# sheet3_nRF52832.net
KiCad netlist of a schematic drawn in Altium Designer
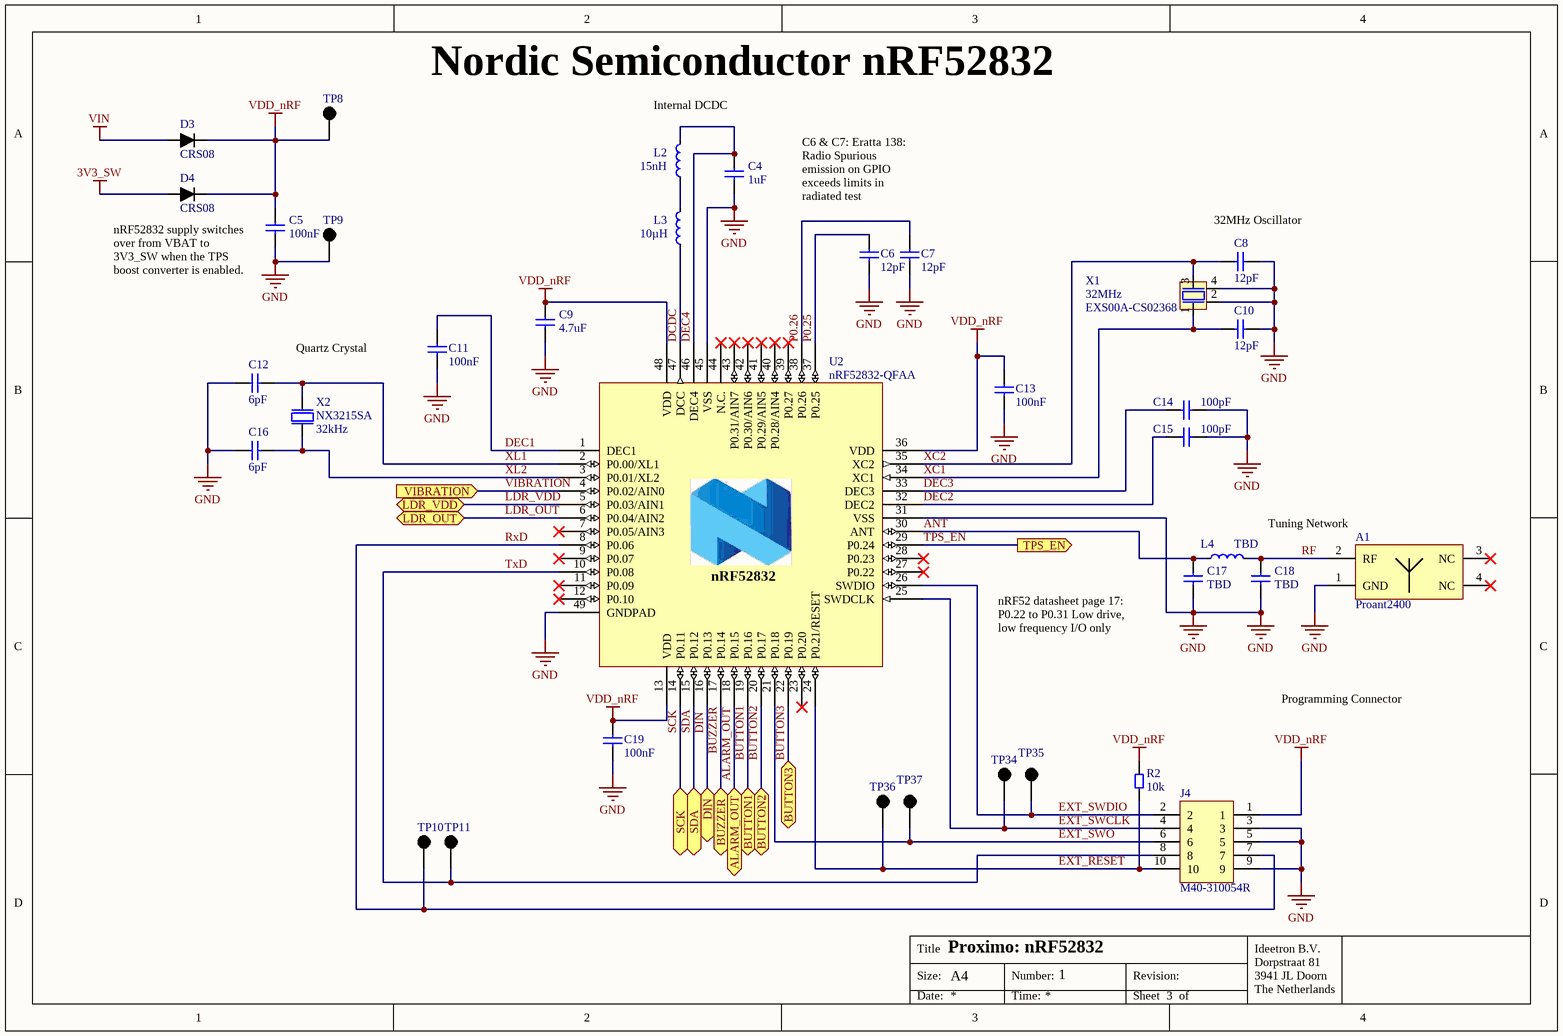
[diagram p0: sheet3_nRF52832.SchDoc]

(export (version "E")
  (design (tool "Eeschema 10.0.6"))
  (components
    (comp (ref "A1")
      (value "Proant2400")
      (footprint "Proant2400")
      (description "Onboard SMD 2400 MHz Antenna for BLE, WLAN/Wifi")
      (fields (field (name "MANUFACTURER") "Proant") (field (name "MANUFACTURER PART NUMBER") "PRO-OB-440"))
      (libsource (lib "Schlib") (part "Proant2400"))
    )
    (comp (ref "C4")
      (value "1uF")
      (footprint "CAP0603_GR18_MURATA")
      (description "Capacitor 1uF X5R 0603 Murata")
      (fields
        (field (name "MANUFACTURER") "Murata")
        (field (name "MANUFACTURER PART NUMBER") "GRM188R61E105KA12D")
      )
      (libsource (lib "Schlib") (part "CAP_0603_1uF"))
    )
    (comp (ref "C5")
      (value "100nF")
      (footprint "CAP0603_GCx18_MURATA")
      (description "Capacitor 0603 100nF")
      (fields
        (field (name "MANUFACTURER") "Murata")
        (field (name "MANUFACTURER PART NUMBER") "GCJ188R71C104KA01D")
      )
      (libsource (lib "Schlib") (part "CAP_0603_100nF"))
    )
    (comp (ref "C6")
      (value "12pF")
      (footprint "CAP0402_GCx15_Murata")
      (description "Capacitor NP0 0402")
      (fields
        (field (name "MANUFACTURER") "Murata")
        (field (name "MANUFACTURER PART NUMBER") "GCM1555C1H120JA16D")
      )
      (libsource (lib "Schlib") (part "CAP_0402_12pF"))
    )
    (comp (ref "C7")
      (value "12pF")
      (footprint "CAP0402_GCx15_Murata")
      (description "Capacitor NP0 0402")
      (fields
        (field (name "MANUFACTURER") "Murata")
        (field (name "MANUFACTURER PART NUMBER") "GCM1555C1H120JA16D")
      )
      (libsource (lib "Schlib") (part "CAP_0402_12pF"))
    )
    (comp (ref "C8")
      (value "12pF")
      (footprint "CAP0402_GCx15_Murata")
      (description "Capacitor NP0 0402")
      (fields
        (field (name "MANUFACTURER") "Murata")
        (field (name "MANUFACTURER PART NUMBER") "GCM1555C1H120JA16D")
      )
      (libsource (lib "Schlib") (part "CAP_0402_12pF"))
    )
    (comp (ref "C9")
      (value "4.7uF")
      (footprint "CAP0603_GR18_MURATA")
      (description "Capacitor X5R 0603 Murata")
      (fields
        (field (name "MANUFACTURER") "Murata")
        (field (name "MANUFACTURER PART NUMBER") "GRM188R60J475KE19D")
      )
      (libsource (lib "Schlib") (part "CAP_0603_4u7"))
    )
    (comp (ref "C10")
      (value "12pF")
      (footprint "CAP0402_GCx15_Murata")
      (description "Capacitor NP0 0402")
      (fields
        (field (name "MANUFACTURER") "Murata")
        (field (name "MANUFACTURER PART NUMBER") "GCM1555C1H120JA16D")
      )
      (libsource (lib "Schlib") (part "CAP_0402_12pF"))
    )
    (comp (ref "C11")
      (value "100nF")
      (footprint "CAP0603_GCx18_MURATA")
      (description "Capacitor 0603 100nF")
      (fields
        (field (name "MANUFACTURER") "Murata")
        (field (name "MANUFACTURER PART NUMBER") "GCJ188R71C104KA01D")
      )
      (libsource (lib "Schlib") (part "CAP_0603_100nF"))
    )
    (comp (ref "C12")
      (value "6pF")
      (footprint "CAP0603_GCx18_MURATA")
      (description "Capacitor NP0 0603 50V")
      (fields (field (name "PART NUMBER") "GCM1885C1H6R0CA16D") (field (name "MANUFACTURER") "Murata"))
      (libsource (lib "Schlib") (part "CAP_0603_6pF"))
    )
    (comp (ref "C13")
      (value "100nF")
      (footprint "CAP0603_GCx18_MURATA")
      (description "Capacitor 0603 100nF")
      (fields
        (field (name "MANUFACTURER") "Murata")
        (field (name "MANUFACTURER PART NUMBER") "GCJ188R71C104KA01D")
      )
      (libsource (lib "Schlib") (part "CAP_0603_100nF"))
    )
    (comp (ref "C14")
      (value "100pF")
      (footprint "CAP0603_GCx18_MURATA")
      (description "Capacitor 100pF 0603 NP0")
      (fields
        (field (name "MANUFACTURER") "Murata")
        (field (name "MANUFACTURER PART NUMBER") "GCM1885C1H101JA16D")
      )
      (libsource (lib "Schlib") (part "CAP_0603_100pF"))
    )
    (comp (ref "C15")
      (value "100pF")
      (footprint "CAP0603_GCx18_MURATA")
      (description "Capacitor 100pF 0603 NP0")
      (fields
        (field (name "MANUFACTURER") "Murata")
        (field (name "MANUFACTURER PART NUMBER") "GCM1885C1H101JA16D")
      )
      (libsource (lib "Schlib") (part "CAP_0603_100pF"))
    )
    (comp (ref "C16")
      (value "6pF")
      (footprint "CAP0603_GCx18_MURATA")
      (description "Capacitor NP0 0603 50V")
      (fields (field (name "PART NUMBER") "GCM1885C1H6R0CA16D") (field (name "MANUFACTURER") "Murata"))
      (libsource (lib "Schlib") (part "CAP_0603_6pF"))
    )
    (comp (ref "C17")
      (value "TBD")
      (footprint "CAPC1005X04L")
      (description "Capacitor, 0402")
      (libsource (lib "Schlib") (part "CAP_0402"))
    )
    (comp (ref "C18")
      (value "TBD")
      (footprint "CAPC1005X04L")
      (description "Capacitor, 0402")
      (libsource (lib "Schlib") (part "CAP_0402"))
    )
    (comp (ref "C19")
      (value "100nF")
      (footprint "CAP0603_GCx18_MURATA")
      (description "Capacitor 0603 100nF")
      (fields
        (field (name "MANUFACTURER") "Murata")
        (field (name "MANUFACTURER PART NUMBER") "GCJ188R71C104KA01D")
      )
      (libsource (lib "Schlib") (part "CAP_0603_100nF"))
    )
    (comp (ref "D3")
      (value "CRS08")
      (footprint "SOD-123F")
      (description "CRS08 Schottky Diode")
      (fields (field (name "MANUFACTURER") "Tohsiba"))
      (libsource (lib "Schlib") (part "CRS08 Schottky Diode"))
    )
    (comp (ref "D4")
      (value "CRS08")
      (footprint "SOD-123F")
      (description "CRS08 Schottky Diode")
      (fields (field (name "MANUFACTURER") "Tohsiba"))
      (libsource (lib "Schlib") (part "CRS08 Schottky Diode"))
    )
    (comp (ref "J4")
      (value "M40-310054R")
      (footprint "Harwin connector")
      (description "Harwin connector 2Rows x 6 contacts M40-3100545R")
      (fields (field (name "MANUFACTURER") "Harwin"))
      (libsource (lib "Schlib") (part "Harwin Connector"))
    )
    (comp (ref "L2")
      (value "15nH")
      (footprint "WE-MK_0402A")
      (description "WE-MK Multilayer Ceramic SMD Inductor, size 0402A, 15nH")
      (fields
        (field (name "PARTNUMBER") "744784115A")
        (field (name "MANUFACTURER") "Wurth Elektronik")
        (field (name "PUBLISHER") "Wurth Elektronik")
      )
      (libsource (lib "Schlib") (part "WE-MK, 744784115A"))
    )
    (comp (ref "L3")
      (value "10µH")
      (footprint "74479777xxx_0805")
      (description "WE-PMI Power Multilayer Inductor, L= 10.0µH")
      (fields
        (field (name "PARTNO") "74479777310A")
        (field (name "MANUFACTURER") "Wurth Elektronik")
        (field (name "CREATED BY") "Baojun Chen")
      )
      (libsource (lib "Schlib") (part "WE-PMI 0805, 74479777310A"))
    )
    (comp (ref "L4")
      (value "TBD")
      (footprint "INDC1005X04L")
      (description "High frequency chip inductor")
      (fields (field (name "2ND SOURCE PART NUMBER") "658-1328"))
      (libsource (lib "Schlib") (part "IND_0402"))
    )
    (comp (ref "R2")
      (value "10k")
      (footprint "RES0603VISHAY")
      (description "SMD Resistor 10k 0603")
      (fields
        (field (name "MANUFACTURER") "Vishay")
        (field (name "MANUFACTURER PART NUMBER") "CRCW060310K0FKTABC")
      )
      (libsource (lib "Schlib") (part "Resistor_10k"))
    )
    (comp (ref "TP8")
      (value "testpad")
      (footprint "TestPad")
      (description "Signal probe pad")
      (libsource (lib "Schlib") (part "TestPad"))
    )
    (comp (ref "TP9")
      (value "testpad")
      (footprint "TestPad")
      (description "Signal probe pad")
      (libsource (lib "Schlib") (part "TestPad"))
    )
    (comp (ref "TP10")
      (value "testpad")
      (footprint "TestPad")
      (description "Signal probe pad")
      (libsource (lib "Schlib") (part "TestPad"))
    )
    (comp (ref "TP11")
      (value "testpad")
      (footprint "TestPad")
      (description "Signal probe pad")
      (libsource (lib "Schlib") (part "TestPad"))
    )
    (comp (ref "TP34")
      (value "testpad")
      (footprint "TestPad")
      (description "Signal probe pad")
      (libsource (lib "Schlib") (part "TestPad"))
    )
    (comp (ref "TP35")
      (value "testpad")
      (footprint "TestPad")
      (description "Signal probe pad")
      (libsource (lib "Schlib") (part "TestPad"))
    )
    (comp (ref "TP36")
      (value "testpad")
      (footprint "TestPad")
      (description "Signal probe pad")
      (libsource (lib "Schlib") (part "TestPad"))
    )
    (comp (ref "TP37")
      (value "testpad")
      (footprint "TestPad")
      (description "Signal probe pad")
      (libsource (lib "Schlib") (part "TestPad"))
    )
    (comp (ref "U2")
      (value "nRF52832-QFAA")
      (footprint "QFN40P600X600X90-48N")
      (description "Multi-protocol Bluetooth Low Energy, ANT and 2.4GHz proprietary system-on-chip")
      (fields
        (field (name "MANUFACTURER") "Nordic Semiconductor")
        (field (name "PUBLISHER") "Nordic Semiconductor")
      )
      (libsource (lib "Schlib") (part "nRF52832_QFAA"))
    )
    (comp (ref "X1")
      (value "EXS00A-CS02368")
      (footprint "NDK-32MHz-XTAL")
      (description "NDK  NX3225SA 32MHz Oscillator")
      (fields
        (field (name "MANUFACTURER") "NDK")
        (field (name "MANUFACTURER PART NUMBER") "NX3225SA")
        (field (name "FREQUENCY") "32MHz")
      )
      (libsource (lib "Schlib") (part "NDK_32MHZ_OCILLATOR"))
    )
    (comp (ref "X2")
      (value "NX3215SA")
      (footprint "XTAL_3215")
      (description "XTAL SMD 3215, 32.768kHz, Cl=9pF, Total Tol: ±50ppm")
      (fields
        (field (name "PART NUMBER") "XTAL_FC-135 32.768k")
        (field (name "MANUFACTURER") "NDK")
        (field (name "FREQUENCY") "32kHz")
      )
      (libsource (lib "Schlib") (part "NDK_32kHz"))
    )
  )
  (nets
    (net (code "1") (name "/ALARM_OUT") (class "Default")
      (node (ref "U2") (pin "18") (pinfunction "P0.15_18") (pintype "bidirectional"))
    )
    (net (code "2") (name "/ANT") (class "Default")
      (node (ref "C17") (pin "2") (pinfunction "2_2") (pintype "passive"))
      (node (ref "L4") (pin "1") (pinfunction "1_1") (pintype "passive"))
      (node (ref "U2") (pin "30") (pinfunction "ANT_30") (pintype "bidirectional"))
    )
    (net (code "3") (name "/BUTTON1") (class "Default")
      (node (ref "U2") (pin "19") (pinfunction "P0.16_19") (pintype "bidirectional"))
    )
    (net (code "4") (name "/BUTTON2") (class "Default")
      (node (ref "U2") (pin "20") (pinfunction "P0.17_20") (pintype "bidirectional"))
    )
    (net (code "5") (name "/BUTTON3") (class "Default")
      (node (ref "U2") (pin "22") (pinfunction "P0.19_22") (pintype "bidirectional"))
    )
    (net (code "6") (name "/BUZZER") (class "Default")
      (node (ref "U2") (pin "17") (pinfunction "P0.14_17") (pintype "bidirectional"))
    )
    (net (code "7") (name "/DCDC") (class "Default")
      (node (ref "L3") (pin "1") (pinfunction "1_1") (pintype "passive"))
      (node (ref "U2") (pin "47") (pinfunction "DCC_47") (pintype "output"))
    )
    (net (code "8") (name "/DEC1") (class "Default")
      (node (ref "C11") (pin "2") (pinfunction "2_2") (pintype "passive"))
      (node (ref "U2") (pin "1") (pinfunction "DEC1_1") (pintype "power_in"))
    )
    (net (code "9") (name "/DEC2") (class "Default")
      (node (ref "C15") (pin "1") (pinfunction "1_1") (pintype "passive"))
      (node (ref "U2") (pin "32") (pinfunction "DEC2_32") (pintype "power_in"))
    )
    (net (code "10") (name "/DEC3") (class "Default")
      (node (ref "C14") (pin "1") (pinfunction "1_1") (pintype "passive"))
      (node (ref "U2") (pin "33") (pinfunction "DEC3_33") (pintype "power_in"))
    )
    (net (code "11") (name "/DEC4") (class "Default")
      (node (ref "C4") (pin "2") (pinfunction "2_2") (pintype "passive"))
      (node (ref "L2") (pin "2") (pinfunction "2_2") (pintype "passive"))
      (node (ref "U2") (pin "46") (pinfunction "DEC4_46") (pintype "power_in"))
    )
    (net (code "12") (name "/DIN") (class "Default")
      (node (ref "U2") (pin "16") (pinfunction "P0.13_16") (pintype "bidirectional"))
    )
    (net (code "13") (name "/EXT_RESET") (class "Default")
      (node (ref "J4") (pin "10") (pinfunction "10_10") (pintype "passive"))
      (node (ref "R2") (pin "1") (pinfunction "1_1") (pintype "passive"))
      (node (ref "TP36") (pin "1") (pinfunction "1_1") (pintype "passive"))
      (node (ref "U2") (pin "24") (pinfunction "P0.21/RESET_24") (pintype "bidirectional"))
    )
    (net (code "14") (name "/EXT_SWCLK") (class "Default")
      (node (ref "J4") (pin "4") (pinfunction "4_4") (pintype "passive"))
      (node (ref "TP34") (pin "1") (pinfunction "1_1") (pintype "passive"))
      (node (ref "U2") (pin "25") (pinfunction "SWDCLK_25") (pintype "input"))
    )
    (net (code "15") (name "/EXT_SWDIO") (class "Default")
      (node (ref "J4") (pin "2") (pinfunction "2_2") (pintype "passive"))
      (node (ref "TP35") (pin "1") (pinfunction "1_1") (pintype "passive"))
      (node (ref "U2") (pin "26") (pinfunction "SWDIO_26") (pintype "bidirectional"))
    )
    (net (code "16") (name "/EXT_SWO") (class "Default")
      (node (ref "J4") (pin "6") (pinfunction "6_6") (pintype "passive"))
      (node (ref "TP37") (pin "1") (pinfunction "1_1") (pintype "passive"))
      (node (ref "U2") (pin "21") (pinfunction "P0.18_21") (pintype "bidirectional"))
    )
    (net (code "17") (name "/LDR_OUT") (class "Default")
      (node (ref "U2") (pin "6") (pinfunction "P0.04/AIN2_6") (pintype "bidirectional"))
    )
    (net (code "18") (name "/LDR_VDD") (class "Default")
      (node (ref "U2") (pin "5") (pinfunction "P0.03/AIN1_5") (pintype "bidirectional"))
    )
    (net (code "19") (name "/P0.25") (class "Default")
      (node (ref "C6") (pin "2") (pinfunction "2_2") (pintype "passive"))
      (node (ref "U2") (pin "37") (pinfunction "P0.25_37") (pintype "bidirectional"))
    )
    (net (code "20") (name "/P0.26") (class "Default")
      (node (ref "C7") (pin "2") (pinfunction "2_2") (pintype "passive"))
      (node (ref "U2") (pin "38") (pinfunction "P0.26_38") (pintype "bidirectional"))
    )
    (net (code "21") (name "/RF") (class "Default")
      (node (ref "A1") (pin "2") (pinfunction "RF_2") (pintype "passive"))
      (node (ref "C18") (pin "2") (pinfunction "2_2") (pintype "passive"))
      (node (ref "L4") (pin "2") (pinfunction "2_2") (pintype "passive"))
    )
    (net (code "22") (name "/RxD") (class "Default")
      (node (ref "J4") (pin "7") (pinfunction "7_7") (pintype "passive"))
      (node (ref "TP10") (pin "1") (pinfunction "1_1") (pintype "passive"))
      (node (ref "U2") (pin "8") (pinfunction "P0.06_8") (pintype "bidirectional"))
    )
    (net (code "23") (name "/SCK") (class "Default")
      (node (ref "U2") (pin "14") (pinfunction "P0.11_14") (pintype "bidirectional"))
    )
    (net (code "24") (name "/SDA") (class "Default")
      (node (ref "U2") (pin "15") (pinfunction "P0.12_15") (pintype "bidirectional"))
    )
    (net (code "25") (name "/TPS_EN") (class "Default")
      (node (ref "U2") (pin "29") (pinfunction "P0.24_29") (pintype "bidirectional"))
    )
    (net (code "26") (name "/TxD") (class "Default")
      (node (ref "J4") (pin "8") (pinfunction "8_8") (pintype "passive"))
      (node (ref "TP11") (pin "1") (pinfunction "1_1") (pintype "passive"))
      (node (ref "U2") (pin "10") (pinfunction "P0.08_10") (pintype "bidirectional"))
    )
    (net (code "27") (name "/VIBRATION") (class "Default")
      (node (ref "U2") (pin "4") (pinfunction "P0.02/AIN0_4") (pintype "bidirectional"))
    )
    (net (code "28") (name "/XC1") (class "Default")
      (node (ref "C10") (pin "2") (pinfunction "2_2") (pintype "passive"))
      (node (ref "U2") (pin "34") (pinfunction "XC1_34") (pintype "input"))
      (node (ref "X1") (pin "1") (pinfunction "inp_1") (pintype "passive"))
    )
    (net (code "29") (name "/XC2") (class "Default")
      (node (ref "C8") (pin "2") (pinfunction "2_2") (pintype "passive"))
      (node (ref "U2") (pin "35") (pinfunction "XC2_35") (pintype "output"))
      (node (ref "X1") (pin "3") (pinfunction "out_3") (pintype "passive"))
    )
    (net (code "30") (name "/XL1") (class "Default")
      (node (ref "C12") (pin "2") (pinfunction "2_2") (pintype "passive"))
      (node (ref "U2") (pin "2") (pinfunction "P0.00/XL1_2") (pintype "bidirectional"))
      (node (ref "X2") (pin "2") (pinfunction "out_2") (pintype "passive"))
    )
    (net (code "31") (name "/XL2") (class "Default")
      (node (ref "C16") (pin "2") (pinfunction "2_2") (pintype "passive"))
      (node (ref "U2") (pin "3") (pinfunction "P0.01/XL2_3") (pintype "bidirectional"))
      (node (ref "X2") (pin "1") (pinfunction "inp_1") (pintype "passive"))
    )
    (net (code "32") (name "3V3_SW") (class "Default")
      (node (ref "D4") (pin "A") (pinfunction "A_A") (pintype "passive"))
    )
    (net (code "33") (name "GND") (class "Default")
      (node (ref "A1") (pin "1") (pinfunction "GND_1") (pintype "passive"))
      (node (ref "C10") (pin "1") (pinfunction "1_1") (pintype "passive"))
      (node (ref "C11") (pin "1") (pinfunction "1_1") (pintype "passive"))
      (node (ref "C12") (pin "1") (pinfunction "1_1") (pintype "passive"))
      (node (ref "C13") (pin "1") (pinfunction "1_1") (pintype "passive"))
      (node (ref "C14") (pin "2") (pinfunction "2_2") (pintype "passive"))
      (node (ref "C15") (pin "2") (pinfunction "2_2") (pintype "passive"))
      (node (ref "C16") (pin "1") (pinfunction "1_1") (pintype "passive"))
      (node (ref "C17") (pin "1") (pinfunction "1_1") (pintype "passive"))
      (node (ref "C18") (pin "1") (pinfunction "1_1") (pintype "passive"))
      (node (ref "C19") (pin "1") (pinfunction "1_1") (pintype "passive"))
      (node (ref "C4") (pin "1") (pinfunction "1_1") (pintype "passive"))
      (node (ref "C5") (pin "1") (pinfunction "1_1") (pintype "passive"))
      (node (ref "C6") (pin "1") (pinfunction "1_1") (pintype "passive"))
      (node (ref "C7") (pin "1") (pinfunction "1_1") (pintype "passive"))
      (node (ref "C8") (pin "1") (pinfunction "1_1") (pintype "passive"))
      (node (ref "C9") (pin "1") (pinfunction "1_1") (pintype "passive"))
      (node (ref "J4") (pin "3") (pinfunction "3_3") (pintype "passive"))
      (node (ref "J4") (pin "5") (pinfunction "5_5") (pintype "passive"))
      (node (ref "J4") (pin "9") (pinfunction "9_9") (pintype "passive"))
      (node (ref "TP9") (pin "1") (pinfunction "1_1") (pintype "passive"))
      (node (ref "U2") (pin "31") (pinfunction "VSS_31") (pintype "power_in"))
      (node (ref "U2") (pin "45") (pinfunction "VSS_45") (pintype "power_in"))
      (node (ref "U2") (pin "49") (pinfunction "GNDPAD_49") (pintype "power_in"))
      (node (ref "X1") (pin "2") (pinfunction "GND_2") (pintype "passive"))
      (node (ref "X1") (pin "4") (pinfunction "GND_4") (pintype "passive"))
    )
    (net (code "34") (name "Net-(L2-Pad1)") (class "Default")
      (node (ref "L2") (pin "1") (pinfunction "1_1") (pintype "passive"))
      (node (ref "L3") (pin "2") (pinfunction "2_2") (pintype "passive"))
    )
    (net (code "35") (name "VDD_nRF") (class "Default")
      (node (ref "C13") (pin "2") (pinfunction "2_2") (pintype "passive"))
      (node (ref "C19") (pin "2") (pinfunction "2_2") (pintype "passive"))
      (node (ref "C5") (pin "2") (pinfunction "2_2") (pintype "passive"))
      (node (ref "C9") (pin "2") (pinfunction "2_2") (pintype "passive"))
      (node (ref "D3") (pin "C") (pinfunction "C_C") (pintype "passive"))
      (node (ref "D4") (pin "C") (pinfunction "C_C") (pintype "passive"))
      (node (ref "J4") (pin "1") (pinfunction "1_1") (pintype "passive"))
      (node (ref "R2") (pin "2") (pinfunction "2_2") (pintype "passive"))
      (node (ref "TP8") (pin "1") (pinfunction "1_1") (pintype "passive"))
      (node (ref "U2") (pin "13") (pinfunction "VDD_13") (pintype "power_in"))
      (node (ref "U2") (pin "36") (pinfunction "VDD_36") (pintype "power_in"))
      (node (ref "U2") (pin "48") (pinfunction "VDD_48") (pintype "power_in"))
    )
    (net (code "36") (name "VIN") (class "Default")
      (node (ref "D3") (pin "A") (pinfunction "A_A") (pintype "passive"))
    )
    (net (code "37") (name "unconnected-(A1-NC-Pad3)") (class "Default")
      (node (ref "A1") (pin "3") (pinfunction "NC_3") (pintype "passive+no_connect"))
    )
    (net (code "38") (name "unconnected-(A1-NC-Pad4)") (class "Default")
      (node (ref "A1") (pin "4") (pinfunction "NC_4") (pintype "passive+no_connect"))
    )
    (net (code "39") (name "unconnected-(U2-N.C.-Pad44)") (class "Default")
      (node (ref "U2") (pin "44") (pinfunction "N.C._44") (pintype "power_in+no_connect"))
    )
    (net (code "40") (name "unconnected-(U2-P0.05{slash}AIN3-Pad7)") (class "Default")
      (node (ref "U2") (pin "7") (pinfunction "P0.05/AIN3_7") (pintype "bidirectional+no_connect"))
    )
    (net (code "41") (name "unconnected-(U2-P0.07-Pad9)") (class "Default")
      (node (ref "U2") (pin "9") (pinfunction "P0.07_9") (pintype "bidirectional+no_connect"))
    )
    (net (code "42") (name "unconnected-(U2-P0.09-Pad11)") (class "Default")
      (node (ref "U2") (pin "11") (pinfunction "P0.09_11") (pintype "bidirectional+no_connect"))
    )
    (net (code "43") (name "unconnected-(U2-P0.10-Pad12)") (class "Default")
      (node (ref "U2") (pin "12") (pinfunction "P0.10_12") (pintype "bidirectional+no_connect"))
    )
    (net (code "44") (name "unconnected-(U2-P0.20-Pad23)") (class "Default")
      (node (ref "U2") (pin "23") (pinfunction "P0.20_23") (pintype "bidirectional+no_connect"))
    )
    (net (code "45") (name "unconnected-(U2-P0.22-Pad27)") (class "Default")
      (node (ref "U2") (pin "27") (pinfunction "P0.22_27") (pintype "bidirectional+no_connect"))
    )
    (net (code "46") (name "unconnected-(U2-P0.23-Pad28)") (class "Default")
      (node (ref "U2") (pin "28") (pinfunction "P0.23_28") (pintype "bidirectional+no_connect"))
    )
    (net (code "47") (name "unconnected-(U2-P0.27-Pad39)") (class "Default")
      (node (ref "U2") (pin "39") (pinfunction "P0.27_39") (pintype "bidirectional+no_connect"))
    )
    (net (code "48") (name "unconnected-(U2-P0.28{slash}AIN4-Pad40)") (class "Default")
      (node (ref "U2") (pin "40") (pinfunction "P0.28/AIN4_40") (pintype "bidirectional+no_connect"))
    )
    (net (code "49") (name "unconnected-(U2-P0.29{slash}AIN5-Pad41)") (class "Default")
      (node (ref "U2") (pin "41") (pinfunction "P0.29/AIN5_41") (pintype "bidirectional+no_connect"))
    )
    (net (code "50") (name "unconnected-(U2-P0.30{slash}AIN6-Pad42)") (class "Default")
      (node (ref "U2") (pin "42") (pinfunction "P0.30/AIN6_42") (pintype "bidirectional+no_connect"))
    )
    (net (code "51") (name "unconnected-(U2-P0.31{slash}AIN7-Pad43)") (class "Default")
      (node (ref "U2") (pin "43") (pinfunction "P0.31/AIN7_43") (pintype "bidirectional+no_connect"))
    )
  )
)
